# PF5c_Filter1B.net
KiCad netlist of a schematic drawn in Altium Designer
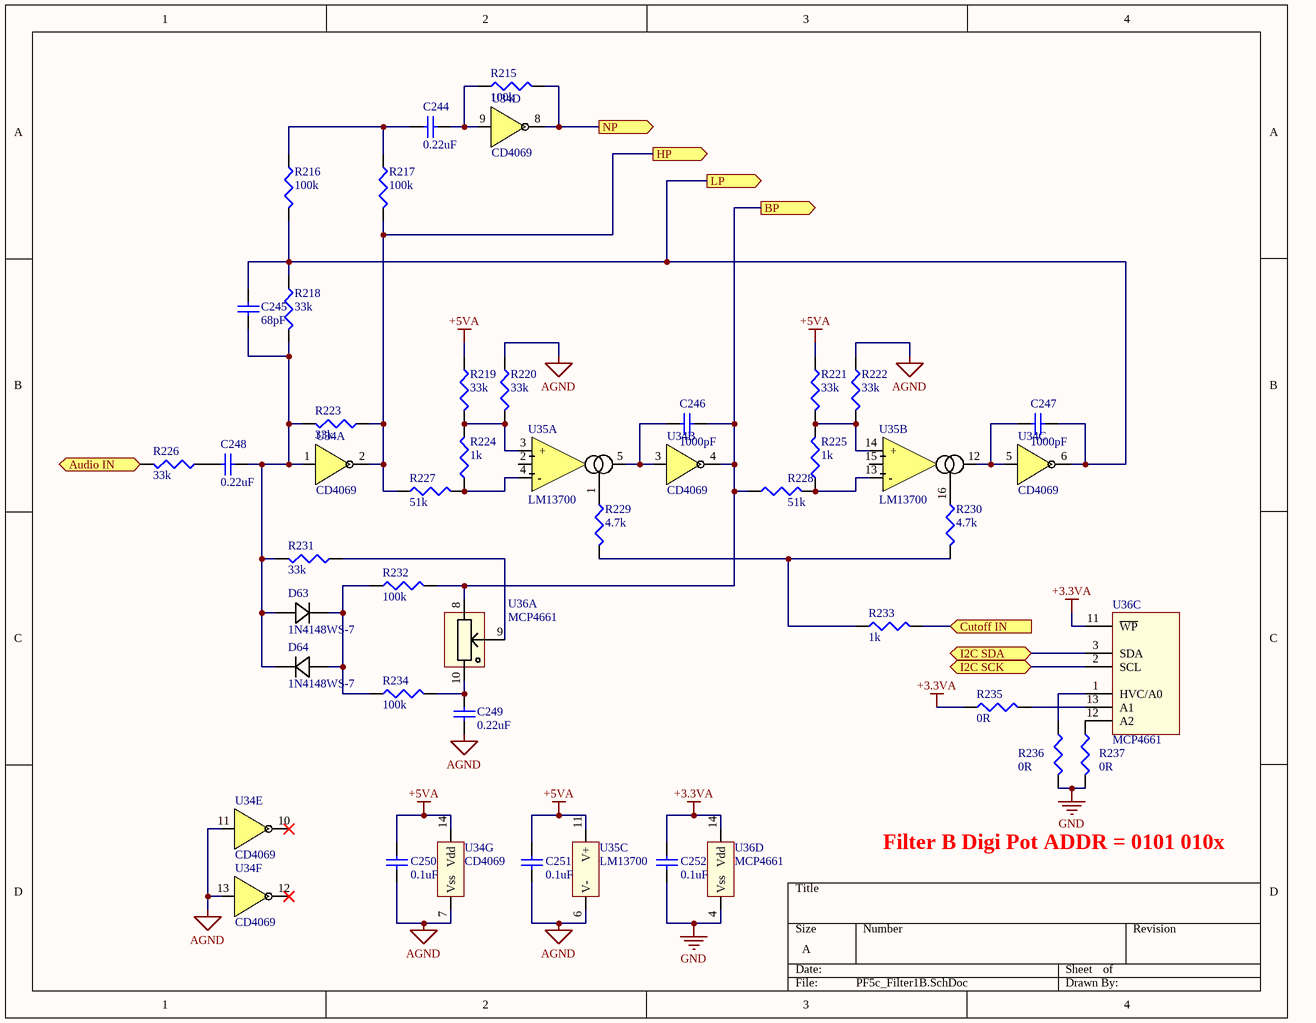
[diagram p0: PF5c_Filter1B.SchDoc]

(export (version "E")
  (design (tool "Eeschema 10.0.6"))
  (components
    (comp (ref "C244")
      (value "0.22uF")
      (footprint "CAPC1608X08")
      (description "Capacitor (Semiconductor SIM Model)")
      (libsource (lib "Michel") (part "Cap Semi"))
    )
    (comp (ref "C245")
      (value "68pF")
      (footprint "CAPC1608X08")
      (description "Capacitor (Semiconductor SIM Model)")
      (libsource (lib "Michel") (part "Cap Semi"))
    )
    (comp (ref "C246")
      (value "1000pF")
      (footprint "CAPC1608X08")
      (description "Capacitor (Semiconductor SIM Model)")
      (libsource (lib "Michel") (part "Cap Semi"))
    )
    (comp (ref "C247")
      (value "1000pF")
      (footprint "CAPC1608X08")
      (description "Capacitor (Semiconductor SIM Model)")
      (libsource (lib "Michel") (part "Cap Semi"))
    )
    (comp (ref "C248")
      (value "0.22uF")
      (footprint "CAPC1608X08")
      (description "Capacitor (Semiconductor SIM Model)")
      (libsource (lib "Michel") (part "Cap Semi"))
    )
    (comp (ref "C249")
      (value "0.22uF")
      (footprint "CAPC1608X08")
      (description "Capacitor (Semiconductor SIM Model)")
      (libsource (lib "Michel") (part "Cap Semi"))
    )
    (comp (ref "C250")
      (value "0.1uF")
      (footprint "CAPC1608X08")
      (description "Capacitor (Semiconductor SIM Model)")
      (libsource (lib "Michel") (part "Cap Semi"))
    )
    (comp (ref "C251")
      (value "0.1uF")
      (footprint "CAPC1608X08")
      (description "Capacitor (Semiconductor SIM Model)")
      (libsource (lib "Michel") (part "Cap Semi"))
    )
    (comp (ref "C252")
      (value "0.1uF")
      (footprint "CAPC1608X08")
      (description "Capacitor (Semiconductor SIM Model)")
      (libsource (lib "Michel") (part "Cap Semi"))
    )
    (comp (ref "D63")
      (value "1N4148WS-7")
      (footprint "SOD323-M")
      (description "Diode signaux faibles")
      (libsource (lib "Michel") (part "1N4148WS-7"))
    )
    (comp (ref "D64")
      (value "1N4148WS-7")
      (footprint "SOD323-M")
      (description "Diode signaux faibles")
      (libsource (lib "Michel") (part "1N4148WS-7"))
    )
    (comp (ref "R215")
      (value "100k")
      (footprint "RESC1608X05")
      (description "Resistor")
      (libsource (lib "Michel") (part "Res3"))
    )
    (comp (ref "R216")
      (value "100k")
      (footprint "RESC1608X05")
      (description "Resistor")
      (libsource (lib "Michel") (part "Res3"))
    )
    (comp (ref "R217")
      (value "100k")
      (footprint "RESC1608X05")
      (description "Resistor")
      (libsource (lib "Michel") (part "Res3"))
    )
    (comp (ref "R218")
      (value "33k")
      (footprint "RESC1608X05")
      (description "Resistor")
      (libsource (lib "Michel") (part "Res3"))
    )
    (comp (ref "R219")
      (value "33k")
      (footprint "RESC1608X05")
      (description "Resistor")
      (libsource (lib "Michel") (part "Res3"))
    )
    (comp (ref "R220")
      (value "33k")
      (footprint "RESC1608X05")
      (description "Resistor")
      (libsource (lib "Michel") (part "Res3"))
    )
    (comp (ref "R221")
      (value "33k")
      (footprint "RESC1608X05")
      (description "Resistor")
      (libsource (lib "Michel") (part "Res3"))
    )
    (comp (ref "R222")
      (value "33k")
      (footprint "RESC1608X05")
      (description "Resistor")
      (libsource (lib "Michel") (part "Res3"))
    )
    (comp (ref "R223")
      (value "33k")
      (footprint "RESC1608X05")
      (description "Resistor")
      (libsource (lib "Michel") (part "Res3"))
    )
    (comp (ref "R224")
      (value "1k")
      (footprint "RESC1608X05")
      (description "Resistor")
      (libsource (lib "Michel") (part "Res3"))
    )
    (comp (ref "R225")
      (value "1k")
      (footprint "RESC1608X05")
      (description "Resistor")
      (libsource (lib "Michel") (part "Res3"))
    )
    (comp (ref "R226")
      (value "33k")
      (footprint "RESC1608X05")
      (description "Resistor")
      (libsource (lib "Michel") (part "Res3"))
    )
    (comp (ref "R227")
      (value "51k")
      (footprint "RESC1608X05")
      (description "Resistor")
      (libsource (lib "Michel") (part "Res3"))
    )
    (comp (ref "R228")
      (value "51k")
      (footprint "RESC1608X05")
      (description "Resistor")
      (libsource (lib "Michel") (part "Res3"))
    )
    (comp (ref "R229")
      (value "4.7k")
      (footprint "RESC1608X05")
      (description "Resistor")
      (libsource (lib "Michel") (part "Res3"))
    )
    (comp (ref "R230")
      (value "4.7k")
      (footprint "RESC1608X05")
      (description "Resistor")
      (libsource (lib "Michel") (part "Res3"))
    )
    (comp (ref "R231")
      (value "33k")
      (footprint "RESC1608X05")
      (description "Resistor")
      (libsource (lib "Michel") (part "Res3"))
    )
    (comp (ref "R232")
      (value "100k")
      (footprint "RESC1608X05")
      (description "Resistor")
      (libsource (lib "Michel") (part "Res3"))
    )
    (comp (ref "R233")
      (value "1k")
      (footprint "RESC1608X05")
      (description "Resistor")
      (libsource (lib "Michel") (part "Res3"))
    )
    (comp (ref "R234")
      (value "100k")
      (footprint "RESC1608X05")
      (description "Resistor")
      (libsource (lib "Michel") (part "Res3"))
    )
    (comp (ref "R235")
      (value "0R")
      (footprint "RESC1608X05")
      (description "Resistor")
      (libsource (lib "Michel") (part "Res3"))
    )
    (comp (ref "R236")
      (value "0R")
      (footprint "RESC1608X05")
      (description "Resistor")
      (libsource (lib "Michel") (part "Res3"))
    )
    (comp (ref "R237")
      (value "0R")
      (footprint "RESC1608X05")
      (description "Resistor")
      (libsource (lib "Michel") (part "Res3"))
    )
    (comp (ref "U34")
      (value "CD4069")
      (footprint "D14-M")
      (description "Hex Inverter")
      (libsource (lib "Michel") (part "CD4069"))
    )
    (comp (ref "U35")
      (value "LM13700")
      (footprint "SO16NB")
      (description "Dual Transconductance OpAmp")
      (libsource (lib "") (part "LM13700M_1"))
    )
    (comp (ref "U36")
      (value "MCP4661")
      (footprint "TSSOP14_MC-M")
      (description "Dual DigiPot non volatile I2C")
      (libsource (lib "Michel") (part "MCP4661"))
    )
  )
  (nets
    (net (code "1") (name "+3.3VA") (class "Default")
      (node (ref "C252") (pin "1") (pinfunction "1_1") (pintype "passive"))
      (node (ref "R235") (pin "1") (pinfunction "1_1") (pintype "passive"))
      (node (ref "U36") (pin "11") (pinfunction "~{WP}_11") (pintype "passive"))
      (node (ref "U36") (pin "14") (pinfunction "Vdd_14") (pintype "power_in"))
    )
    (net (code "2") (name "+5VA") (class "Default")
      (node (ref "C250") (pin "1") (pinfunction "1_1") (pintype "passive"))
      (node (ref "C251") (pin "1") (pinfunction "1_1") (pintype "passive"))
      (node (ref "R219") (pin "1") (pinfunction "1_1") (pintype "passive"))
      (node (ref "R221") (pin "1") (pinfunction "1_1") (pintype "passive"))
      (node (ref "U34") (pin "14") (pinfunction "Vdd_14") (pintype "power_in"))
      (node (ref "U35") (pin "11") (pinfunction "V+_11") (pintype "power_in"))
    )
    (net (code "3") (name "/Audio IN") (class "Default")
      (node (ref "R226") (pin "2") (pinfunction "2_2") (pintype "passive"))
    )
    (net (code "4") (name "/BP") (class "Default")
      (node (ref "C246") (pin "2") (pinfunction "2_2") (pintype "passive"))
      (node (ref "R228") (pin "1") (pinfunction "1_1") (pintype "passive"))
      (node (ref "R232") (pin "2") (pinfunction "2_2") (pintype "passive"))
      (node (ref "U34") (pin "4") (pinfunction "~{B}_4") (pintype "passive"))
      (node (ref "U36") (pin "8") (pinfunction "P0A_8") (pintype "passive"))
    )
    (net (code "5") (name "/Cutoff IN") (class "Default")
      (node (ref "R233") (pin "2") (pinfunction "2_2") (pintype "passive"))
    )
    (net (code "6") (name "/HP") (class "Default")
      (node (ref "R217") (pin "2") (pinfunction "2_2") (pintype "passive"))
      (node (ref "R223") (pin "1") (pinfunction "1_1") (pintype "passive"))
      (node (ref "R227") (pin "1") (pinfunction "1_1") (pintype "passive"))
      (node (ref "U34") (pin "2") (pinfunction "~{A}_2") (pintype "passive"))
    )
    (net (code "7") (name "/I2C SCK") (class "Default")
      (node (ref "U36") (pin "2") (pinfunction "SCL_2") (pintype "passive"))
    )
    (net (code "8") (name "/I2C SDA") (class "Default")
      (node (ref "U36") (pin "3") (pinfunction "SDA_3") (pintype "passive"))
    )
    (net (code "9") (name "/LP") (class "Default")
      (node (ref "C245") (pin "2") (pinfunction "2_2") (pintype "passive"))
      (node (ref "C247") (pin "2") (pinfunction "2_2") (pintype "passive"))
      (node (ref "R216") (pin "2") (pinfunction "2_2") (pintype "passive"))
      (node (ref "R218") (pin "1") (pinfunction "1_1") (pintype "passive"))
      (node (ref "U34") (pin "6") (pinfunction "~{C}_6") (pintype "passive"))
    )
    (net (code "10") (name "/NP") (class "Default")
      (node (ref "R215") (pin "2") (pinfunction "2_2") (pintype "passive"))
      (node (ref "U34") (pin "8") (pinfunction "~{D}_8") (pintype "passive"))
    )
    (net (code "11") (name "AGND") (class "Default")
      (node (ref "C249") (pin "1") (pinfunction "1_1") (pintype "passive"))
      (node (ref "C250") (pin "2") (pinfunction "2_2") (pintype "passive"))
      (node (ref "C251") (pin "2") (pinfunction "2_2") (pintype "passive"))
      (node (ref "R220") (pin "1") (pinfunction "1_1") (pintype "passive"))
      (node (ref "R222") (pin "1") (pinfunction "1_1") (pintype "passive"))
      (node (ref "U34") (pin "11") (pinfunction "E_11") (pintype "passive"))
      (node (ref "U34") (pin "13") (pinfunction "F_13") (pintype "passive"))
      (node (ref "U34") (pin "7") (pinfunction "Vss_7") (pintype "power_in"))
      (node (ref "U35") (pin "6") (pinfunction "V-_6") (pintype "power_in"))
    )
    (net (code "12") (name "GND") (class "Default")
      (node (ref "C252") (pin "2") (pinfunction "2_2") (pintype "passive"))
      (node (ref "R236") (pin "2") (pinfunction "2_2") (pintype "passive"))
      (node (ref "R237") (pin "2") (pinfunction "2_2") (pintype "passive"))
      (node (ref "U36") (pin "4") (pinfunction "Vss_4") (pintype "power_in"))
    )
    (net (code "13") (name "Net-(C244-Pad2)") (class "Default")
      (node (ref "C244") (pin "2") (pinfunction "2_2") (pintype "passive"))
      (node (ref "R216") (pin "1") (pinfunction "1_1") (pintype "passive"))
      (node (ref "R217") (pin "1") (pinfunction "1_1") (pintype "passive"))
    )
    (net (code "14") (name "Net-(C248-Pad2)") (class "Default")
      (node (ref "C248") (pin "2") (pinfunction "2_2") (pintype "passive"))
      (node (ref "R226") (pin "1") (pinfunction "1_1") (pintype "passive"))
    )
    (net (code "15") (name "Net-(D63-Pad1)") (class "Default")
      (node (ref "D63") (pin "1") (pinfunction "1_1") (pintype "passive"))
      (node (ref "D64") (pin "2") (pinfunction "2_2") (pintype "passive"))
      (node (ref "R232") (pin "1") (pinfunction "1_1") (pintype "passive"))
      (node (ref "R234") (pin "1") (pinfunction "1_1") (pintype "passive"))
    )
    (net (code "16") (name "Net-(R229-Pad2)") (class "Default")
      (node (ref "R229") (pin "2") (pinfunction "2_2") (pintype "passive"))
      (node (ref "R230") (pin "2") (pinfunction "2_2") (pintype "passive"))
      (node (ref "R233") (pin "1") (pinfunction "1_1") (pintype "passive"))
    )
    (net (code "17") (name "Net-(U34A-A)") (class "Default")
      (node (ref "C245") (pin "1") (pinfunction "1_1") (pintype "passive"))
      (node (ref "C248") (pin "1") (pinfunction "1_1") (pintype "passive"))
      (node (ref "D63") (pin "2") (pinfunction "2_2") (pintype "passive"))
      (node (ref "D64") (pin "1") (pinfunction "1_1") (pintype "passive"))
      (node (ref "R218") (pin "2") (pinfunction "2_2") (pintype "passive"))
      (node (ref "R223") (pin "2") (pinfunction "2_2") (pintype "passive"))
      (node (ref "R231") (pin "2") (pinfunction "2_2") (pintype "passive"))
      (node (ref "U34") (pin "1") (pinfunction "A_1") (pintype "passive"))
    )
    (net (code "18") (name "Net-(U34B-B)") (class "Default")
      (node (ref "C246") (pin "1") (pinfunction "1_1") (pintype "passive"))
      (node (ref "U34") (pin "3") (pinfunction "B_3") (pintype "passive"))
      (node (ref "U35") (pin "5") (pinfunction "OUT_5") (pintype "passive"))
    )
    (net (code "19") (name "Net-(U34C-C)") (class "Default")
      (node (ref "C247") (pin "1") (pinfunction "1_1") (pintype "passive"))
      (node (ref "U34") (pin "5") (pinfunction "C_5") (pintype "passive"))
      (node (ref "U35") (pin "12") (pinfunction "OUT_12") (pintype "passive"))
    )
    (net (code "20") (name "Net-(U34D-D)") (class "Default")
      (node (ref "C244") (pin "1") (pinfunction "1_1") (pintype "passive"))
      (node (ref "R215") (pin "1") (pinfunction "1_1") (pintype "passive"))
      (node (ref "U34") (pin "9") (pinfunction "D_9") (pintype "passive"))
    )
    (net (code "21") (name "Net-(U35A-+)") (class "Default")
      (node (ref "R219") (pin "2") (pinfunction "2_2") (pintype "passive"))
      (node (ref "R220") (pin "2") (pinfunction "2_2") (pintype "passive"))
      (node (ref "R224") (pin "2") (pinfunction "2_2") (pintype "passive"))
      (node (ref "U35") (pin "3") (pinfunction "+_3") (pintype "passive"))
    )
    (net (code "22") (name "Net-(U35A--)") (class "Default")
      (node (ref "R224") (pin "1") (pinfunction "1_1") (pintype "passive"))
      (node (ref "R227") (pin "2") (pinfunction "2_2") (pintype "passive"))
      (node (ref "U35") (pin "4") (pinfunction "-_4") (pintype "passive"))
    )
    (net (code "23") (name "Net-(U35A-BIAS)") (class "Default")
      (node (ref "R229") (pin "1") (pinfunction "1_1") (pintype "passive"))
      (node (ref "U35") (pin "1") (pinfunction "BIAS_1") (pintype "passive"))
    )
    (net (code "24") (name "Net-(U35B-+)") (class "Default")
      (node (ref "R221") (pin "2") (pinfunction "2_2") (pintype "passive"))
      (node (ref "R222") (pin "2") (pinfunction "2_2") (pintype "passive"))
      (node (ref "R225") (pin "2") (pinfunction "2_2") (pintype "passive"))
      (node (ref "U35") (pin "14") (pinfunction "+_14") (pintype "passive"))
    )
    (net (code "25") (name "Net-(U35B--)") (class "Default")
      (node (ref "R225") (pin "1") (pinfunction "1_1") (pintype "passive"))
      (node (ref "R228") (pin "2") (pinfunction "2_2") (pintype "passive"))
      (node (ref "U35") (pin "13") (pinfunction "-_13") (pintype "passive"))
    )
    (net (code "26") (name "Net-(U35B-BIAS)") (class "Default")
      (node (ref "R230") (pin "1") (pinfunction "1_1") (pintype "passive"))
      (node (ref "U35") (pin "16") (pinfunction "BIAS_16") (pintype "passive"))
    )
    (net (code "27") (name "Net-(U36A-P0B)") (class "Default")
      (node (ref "C249") (pin "2") (pinfunction "2_2") (pintype "passive"))
      (node (ref "R234") (pin "2") (pinfunction "2_2") (pintype "passive"))
      (node (ref "U36") (pin "10") (pinfunction "P0B_10") (pintype "passive"))
    )
    (net (code "28") (name "Net-(U36A-P0W)") (class "Default")
      (node (ref "R231") (pin "1") (pinfunction "1_1") (pintype "passive"))
      (node (ref "U36") (pin "9") (pinfunction "P0W_9") (pintype "passive"))
    )
    (net (code "29") (name "Net-(U36C-A1)") (class "Default")
      (node (ref "R235") (pin "2") (pinfunction "2_2") (pintype "passive"))
      (node (ref "U36") (pin "13") (pinfunction "A1_13") (pintype "power_in"))
    )
    (net (code "30") (name "Net-(U36C-A2)") (class "Default")
      (node (ref "R237") (pin "1") (pinfunction "1_1") (pintype "passive"))
      (node (ref "U36") (pin "12") (pinfunction "A2_12") (pintype "power_in"))
    )
    (net (code "31") (name "Net-(U36C-HVC{slash}A0)") (class "Default")
      (node (ref "R236") (pin "1") (pinfunction "1_1") (pintype "passive"))
      (node (ref "U36") (pin "1") (pinfunction "HVC/A0_1") (pintype "power_in"))
    )
    (net (code "32") (name "unconnected-(U34E-~{E}-Pad10)") (class "Default")
      (node (ref "U34") (pin "10") (pinfunction "~{E}_10") (pintype "passive+no_connect"))
    )
    (net (code "33") (name "unconnected-(U34F-~{F}-Pad12)") (class "Default")
      (node (ref "U34") (pin "12") (pinfunction "~{F}_12") (pintype "passive+no_connect"))
    )
    (net (code "34") (name "unconnected-(U35A-Diode_BIAS-Pad2)") (class "Default")
      (node (ref "U35") (pin "2") (pinfunction "Diode_BIAS_2") (pintype "passive"))
    )
    (net (code "35") (name "unconnected-(U35B-Diode_BIAS-Pad15)") (class "Default")
      (node (ref "U35") (pin "15") (pinfunction "Diode_BIAS_15") (pintype "passive"))
    )
  )
)
